# Clock.net
KiCad netlist of a schematic drawn in Altium Designer
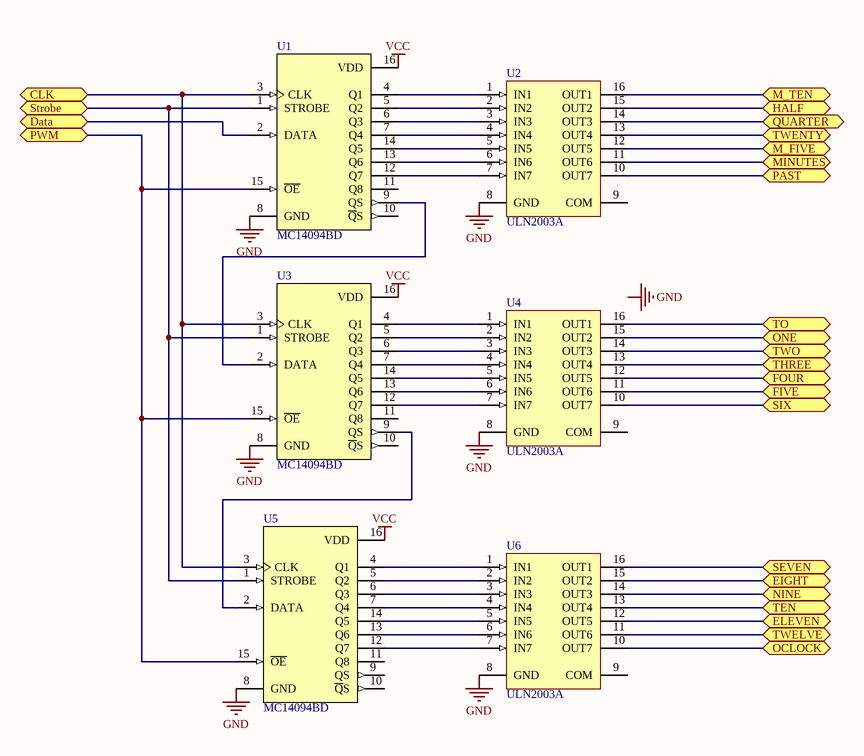
[diagram p0: Clock.SchDoc]

(export (version "E")
  (design (tool "Eeschema 10.0.6"))
  (components
    (comp (ref "U1")
      (value "MC14094BD")
      (footprint "751B-05_N")
      (description "8-Stage Shift/Store Register with 3-State Outputs")
      (fields (field (name "PUBLISHER") "Altium Limited"))
      (libsource (lib "ON Semi Logic Register") (part "MC14094BD"))
    )
    (comp (ref "U2")
      (value "ULN2003A")
      (footprint "DIP16")
      (description "Seven Darlington Array")
      (fields (field (name "PUBLISHER") "Altium Limited"))
      (libsource (lib "ST Interface Darlington Driver") (part "ULN2003A"))
    )
    (comp (ref "U3")
      (value "MC14094BD")
      (footprint "751B-05_N")
      (description "8-Stage Shift/Store Register with 3-State Outputs")
      (fields (field (name "PUBLISHER") "Altium Limited"))
      (libsource (lib "ON Semi Logic Register") (part "MC14094BD"))
    )
    (comp (ref "U4")
      (value "ULN2003A")
      (footprint "DIP16")
      (description "Seven Darlington Array")
      (fields (field (name "PUBLISHER") "Altium Limited"))
      (libsource (lib "ST Interface Darlington Driver") (part "ULN2003A"))
    )
    (comp (ref "U5")
      (value "MC14094BD")
      (footprint "751B-05_N")
      (description "8-Stage Shift/Store Register with 3-State Outputs")
      (fields (field (name "PUBLISHER") "Altium Limited"))
      (libsource (lib "ON Semi Logic Register") (part "MC14094BD"))
    )
    (comp (ref "U6")
      (value "ULN2003A")
      (footprint "DIP16")
      (description "Seven Darlington Array")
      (fields (field (name "PUBLISHER") "Altium Limited"))
      (libsource (lib "ST Interface Darlington Driver") (part "ULN2003A"))
    )
  )
  (nets
    (net (code "1") (name "/CLK") (class "Default")
      (node (ref "U1") (pin "3") (pinfunction "CLK_3") (pintype "input"))
      (node (ref "U3") (pin "3") (pinfunction "CLK_3") (pintype "input"))
      (node (ref "U5") (pin "3") (pinfunction "CLK_3") (pintype "input"))
    )
    (net (code "2") (name "/Data") (class "Default")
      (node (ref "U1") (pin "2") (pinfunction "DATA_2") (pintype "input"))
    )
    (net (code "3") (name "/EIGHT") (class "Default")
      (node (ref "U6") (pin "15") (pinfunction "OUT2_15") (pintype "open_collector"))
    )
    (net (code "4") (name "/ELEVEN") (class "Default")
      (node (ref "U6") (pin "12") (pinfunction "OUT5_12") (pintype "open_collector"))
    )
    (net (code "5") (name "/FIVE") (class "Default")
      (node (ref "U4") (pin "11") (pinfunction "OUT6_11") (pintype "open_collector"))
    )
    (net (code "6") (name "/FOUR") (class "Default")
      (node (ref "U4") (pin "12") (pinfunction "OUT5_12") (pintype "open_collector"))
    )
    (net (code "7") (name "/HALF") (class "Default")
      (node (ref "U2") (pin "15") (pinfunction "OUT2_15") (pintype "open_collector"))
    )
    (net (code "8") (name "/MINUTES") (class "Default")
      (node (ref "U2") (pin "11") (pinfunction "OUT6_11") (pintype "open_collector"))
    )
    (net (code "9") (name "/M_FIVE") (class "Default")
      (node (ref "U2") (pin "12") (pinfunction "OUT5_12") (pintype "open_collector"))
    )
    (net (code "10") (name "/M_TEN") (class "Default")
      (node (ref "U2") (pin "16") (pinfunction "OUT1_16") (pintype "open_collector"))
    )
    (net (code "11") (name "/NINE") (class "Default")
      (node (ref "U6") (pin "14") (pinfunction "OUT3_14") (pintype "open_collector"))
    )
    (net (code "12") (name "/OCLOCK") (class "Default")
      (node (ref "U6") (pin "10") (pinfunction "OUT7_10") (pintype "open_collector"))
    )
    (net (code "13") (name "/ONE") (class "Default")
      (node (ref "U4") (pin "15") (pinfunction "OUT2_15") (pintype "open_collector"))
    )
    (net (code "14") (name "/PAST") (class "Default")
      (node (ref "U2") (pin "10") (pinfunction "OUT7_10") (pintype "open_collector"))
    )
    (net (code "15") (name "/PWM") (class "Default")
      (node (ref "U1") (pin "15") (pinfunction "~{OE}_15") (pintype "input"))
      (node (ref "U3") (pin "15") (pinfunction "~{OE}_15") (pintype "input"))
      (node (ref "U5") (pin "15") (pinfunction "~{OE}_15") (pintype "input"))
    )
    (net (code "16") (name "/QUARTER") (class "Default")
      (node (ref "U2") (pin "14") (pinfunction "OUT3_14") (pintype "open_collector"))
    )
    (net (code "17") (name "/SEVEN") (class "Default")
      (node (ref "U6") (pin "16") (pinfunction "OUT1_16") (pintype "open_collector"))
    )
    (net (code "18") (name "/SIX") (class "Default")
      (node (ref "U4") (pin "10") (pinfunction "OUT7_10") (pintype "open_collector"))
    )
    (net (code "19") (name "/Strobe") (class "Default")
      (node (ref "U1") (pin "1") (pinfunction "STROBE_1") (pintype "input"))
      (node (ref "U3") (pin "1") (pinfunction "STROBE_1") (pintype "input"))
      (node (ref "U5") (pin "1") (pinfunction "STROBE_1") (pintype "input"))
    )
    (net (code "20") (name "/TEN") (class "Default")
      (node (ref "U6") (pin "13") (pinfunction "OUT4_13") (pintype "open_collector"))
    )
    (net (code "21") (name "/THREE") (class "Default")
      (node (ref "U4") (pin "13") (pinfunction "OUT4_13") (pintype "open_collector"))
    )
    (net (code "22") (name "/TO") (class "Default")
      (node (ref "U4") (pin "16") (pinfunction "OUT1_16") (pintype "open_collector"))
    )
    (net (code "23") (name "/TWELVE") (class "Default")
      (node (ref "U6") (pin "11") (pinfunction "OUT6_11") (pintype "open_collector"))
    )
    (net (code "24") (name "/TWENTY") (class "Default")
      (node (ref "U2") (pin "13") (pinfunction "OUT4_13") (pintype "open_collector"))
    )
    (net (code "25") (name "/TWO") (class "Default")
      (node (ref "U4") (pin "14") (pinfunction "OUT3_14") (pintype "open_collector"))
    )
    (net (code "26") (name "GND") (class "Default")
      (node (ref "U1") (pin "8") (pinfunction "GND_8") (pintype "power_in"))
      (node (ref "U2") (pin "8") (pinfunction "GND_8") (pintype "power_in"))
      (node (ref "U3") (pin "8") (pinfunction "GND_8") (pintype "power_in"))
      (node (ref "U4") (pin "8") (pinfunction "GND_8") (pintype "power_in"))
      (node (ref "U5") (pin "8") (pinfunction "GND_8") (pintype "power_in"))
      (node (ref "U6") (pin "8") (pinfunction "GND_8") (pintype "power_in"))
    )
    (net (code "27") (name "Net-(U1-Q1)") (class "Default")
      (node (ref "U1") (pin "4") (pinfunction "Q1_4") (pintype "tri_state"))
      (node (ref "U2") (pin "1") (pinfunction "IN1_1") (pintype "input"))
    )
    (net (code "28") (name "Net-(U1-Q2)") (class "Default")
      (node (ref "U1") (pin "5") (pinfunction "Q2_5") (pintype "tri_state"))
      (node (ref "U2") (pin "2") (pinfunction "IN2_2") (pintype "input"))
    )
    (net (code "29") (name "Net-(U1-Q3)") (class "Default")
      (node (ref "U1") (pin "6") (pinfunction "Q3_6") (pintype "tri_state"))
      (node (ref "U2") (pin "3") (pinfunction "IN3_3") (pintype "input"))
    )
    (net (code "30") (name "Net-(U1-Q4)") (class "Default")
      (node (ref "U1") (pin "7") (pinfunction "Q4_7") (pintype "tri_state"))
      (node (ref "U2") (pin "4") (pinfunction "IN4_4") (pintype "input"))
    )
    (net (code "31") (name "Net-(U1-Q5)") (class "Default")
      (node (ref "U1") (pin "14") (pinfunction "Q5_14") (pintype "tri_state"))
      (node (ref "U2") (pin "5") (pinfunction "IN5_5") (pintype "input"))
    )
    (net (code "32") (name "Net-(U1-Q6)") (class "Default")
      (node (ref "U1") (pin "13") (pinfunction "Q6_13") (pintype "tri_state"))
      (node (ref "U2") (pin "6") (pinfunction "IN6_6") (pintype "input"))
    )
    (net (code "33") (name "Net-(U1-Q7)") (class "Default")
      (node (ref "U1") (pin "12") (pinfunction "Q7_12") (pintype "tri_state"))
      (node (ref "U2") (pin "7") (pinfunction "IN7_7") (pintype "input"))
    )
    (net (code "34") (name "Net-(U1-QS)") (class "Default")
      (node (ref "U1") (pin "9") (pinfunction "QS_9") (pintype "output"))
      (node (ref "U3") (pin "2") (pinfunction "DATA_2") (pintype "input"))
    )
    (net (code "35") (name "Net-(U3-Q1)") (class "Default")
      (node (ref "U3") (pin "4") (pinfunction "Q1_4") (pintype "tri_state"))
      (node (ref "U4") (pin "1") (pinfunction "IN1_1") (pintype "input"))
    )
    (net (code "36") (name "Net-(U3-Q2)") (class "Default")
      (node (ref "U3") (pin "5") (pinfunction "Q2_5") (pintype "tri_state"))
      (node (ref "U4") (pin "2") (pinfunction "IN2_2") (pintype "input"))
    )
    (net (code "37") (name "Net-(U3-Q3)") (class "Default")
      (node (ref "U3") (pin "6") (pinfunction "Q3_6") (pintype "tri_state"))
      (node (ref "U4") (pin "3") (pinfunction "IN3_3") (pintype "input"))
    )
    (net (code "38") (name "Net-(U3-Q4)") (class "Default")
      (node (ref "U3") (pin "7") (pinfunction "Q4_7") (pintype "tri_state"))
      (node (ref "U4") (pin "4") (pinfunction "IN4_4") (pintype "input"))
    )
    (net (code "39") (name "Net-(U3-Q5)") (class "Default")
      (node (ref "U3") (pin "14") (pinfunction "Q5_14") (pintype "tri_state"))
      (node (ref "U4") (pin "5") (pinfunction "IN5_5") (pintype "input"))
    )
    (net (code "40") (name "Net-(U3-Q6)") (class "Default")
      (node (ref "U3") (pin "13") (pinfunction "Q6_13") (pintype "tri_state"))
      (node (ref "U4") (pin "6") (pinfunction "IN6_6") (pintype "input"))
    )
    (net (code "41") (name "Net-(U3-Q7)") (class "Default")
      (node (ref "U3") (pin "12") (pinfunction "Q7_12") (pintype "tri_state"))
      (node (ref "U4") (pin "7") (pinfunction "IN7_7") (pintype "input"))
    )
    (net (code "42") (name "Net-(U3-QS)") (class "Default")
      (node (ref "U3") (pin "9") (pinfunction "QS_9") (pintype "output"))
      (node (ref "U5") (pin "2") (pinfunction "DATA_2") (pintype "input"))
    )
    (net (code "43") (name "Net-(U5-Q1)") (class "Default")
      (node (ref "U5") (pin "4") (pinfunction "Q1_4") (pintype "tri_state"))
      (node (ref "U6") (pin "1") (pinfunction "IN1_1") (pintype "input"))
    )
    (net (code "44") (name "Net-(U5-Q2)") (class "Default")
      (node (ref "U5") (pin "5") (pinfunction "Q2_5") (pintype "tri_state"))
      (node (ref "U6") (pin "2") (pinfunction "IN2_2") (pintype "input"))
    )
    (net (code "45") (name "Net-(U5-Q3)") (class "Default")
      (node (ref "U5") (pin "6") (pinfunction "Q3_6") (pintype "tri_state"))
      (node (ref "U6") (pin "3") (pinfunction "IN3_3") (pintype "input"))
    )
    (net (code "46") (name "Net-(U5-Q4)") (class "Default")
      (node (ref "U5") (pin "7") (pinfunction "Q4_7") (pintype "tri_state"))
      (node (ref "U6") (pin "4") (pinfunction "IN4_4") (pintype "input"))
    )
    (net (code "47") (name "Net-(U5-Q5)") (class "Default")
      (node (ref "U5") (pin "14") (pinfunction "Q5_14") (pintype "tri_state"))
      (node (ref "U6") (pin "5") (pinfunction "IN5_5") (pintype "input"))
    )
    (net (code "48") (name "Net-(U5-Q6)") (class "Default")
      (node (ref "U5") (pin "13") (pinfunction "Q6_13") (pintype "tri_state"))
      (node (ref "U6") (pin "6") (pinfunction "IN6_6") (pintype "input"))
    )
    (net (code "49") (name "Net-(U5-Q7)") (class "Default")
      (node (ref "U5") (pin "12") (pinfunction "Q7_12") (pintype "tri_state"))
      (node (ref "U6") (pin "7") (pinfunction "IN7_7") (pintype "input"))
    )
    (net (code "50") (name "VCC") (class "Default")
      (node (ref "U1") (pin "16") (pinfunction "VDD_16") (pintype "power_in"))
      (node (ref "U3") (pin "16") (pinfunction "VDD_16") (pintype "power_in"))
      (node (ref "U5") (pin "16") (pinfunction "VDD_16") (pintype "power_in"))
    )
    (net (code "51") (name "unconnected-(U1-Q8-Pad11)") (class "Default")
      (node (ref "U1") (pin "11") (pinfunction "Q8_11") (pintype "tri_state"))
    )
    (net (code "52") (name "unconnected-(U1-~{Q}S-Pad10)") (class "Default")
      (node (ref "U1") (pin "10") (pinfunction "~{Q}S_10") (pintype "output"))
    )
    (net (code "53") (name "unconnected-(U2-COM-Pad9)") (class "Default")
      (node (ref "U2") (pin "9") (pinfunction "COM_9") (pintype "passive"))
    )
    (net (code "54") (name "unconnected-(U3-Q8-Pad11)") (class "Default")
      (node (ref "U3") (pin "11") (pinfunction "Q8_11") (pintype "tri_state"))
    )
    (net (code "55") (name "unconnected-(U3-~{Q}S-Pad10)") (class "Default")
      (node (ref "U3") (pin "10") (pinfunction "~{Q}S_10") (pintype "output"))
    )
    (net (code "56") (name "unconnected-(U4-COM-Pad9)") (class "Default")
      (node (ref "U4") (pin "9") (pinfunction "COM_9") (pintype "passive"))
    )
    (net (code "57") (name "unconnected-(U5-Q8-Pad11)") (class "Default")
      (node (ref "U5") (pin "11") (pinfunction "Q8_11") (pintype "tri_state"))
    )
    (net (code "58") (name "unconnected-(U5-QS-Pad9)") (class "Default")
      (node (ref "U5") (pin "9") (pinfunction "QS_9") (pintype "output"))
    )
    (net (code "59") (name "unconnected-(U5-~{Q}S-Pad10)") (class "Default")
      (node (ref "U5") (pin "10") (pinfunction "~{Q}S_10") (pintype "output"))
    )
    (net (code "60") (name "unconnected-(U6-COM-Pad9)") (class "Default")
      (node (ref "U6") (pin "9") (pinfunction "COM_9") (pintype "passive"))
    )
  )
)
